# Motor_Control.net
KiCad netlist of a schematic drawn in Altium Designer
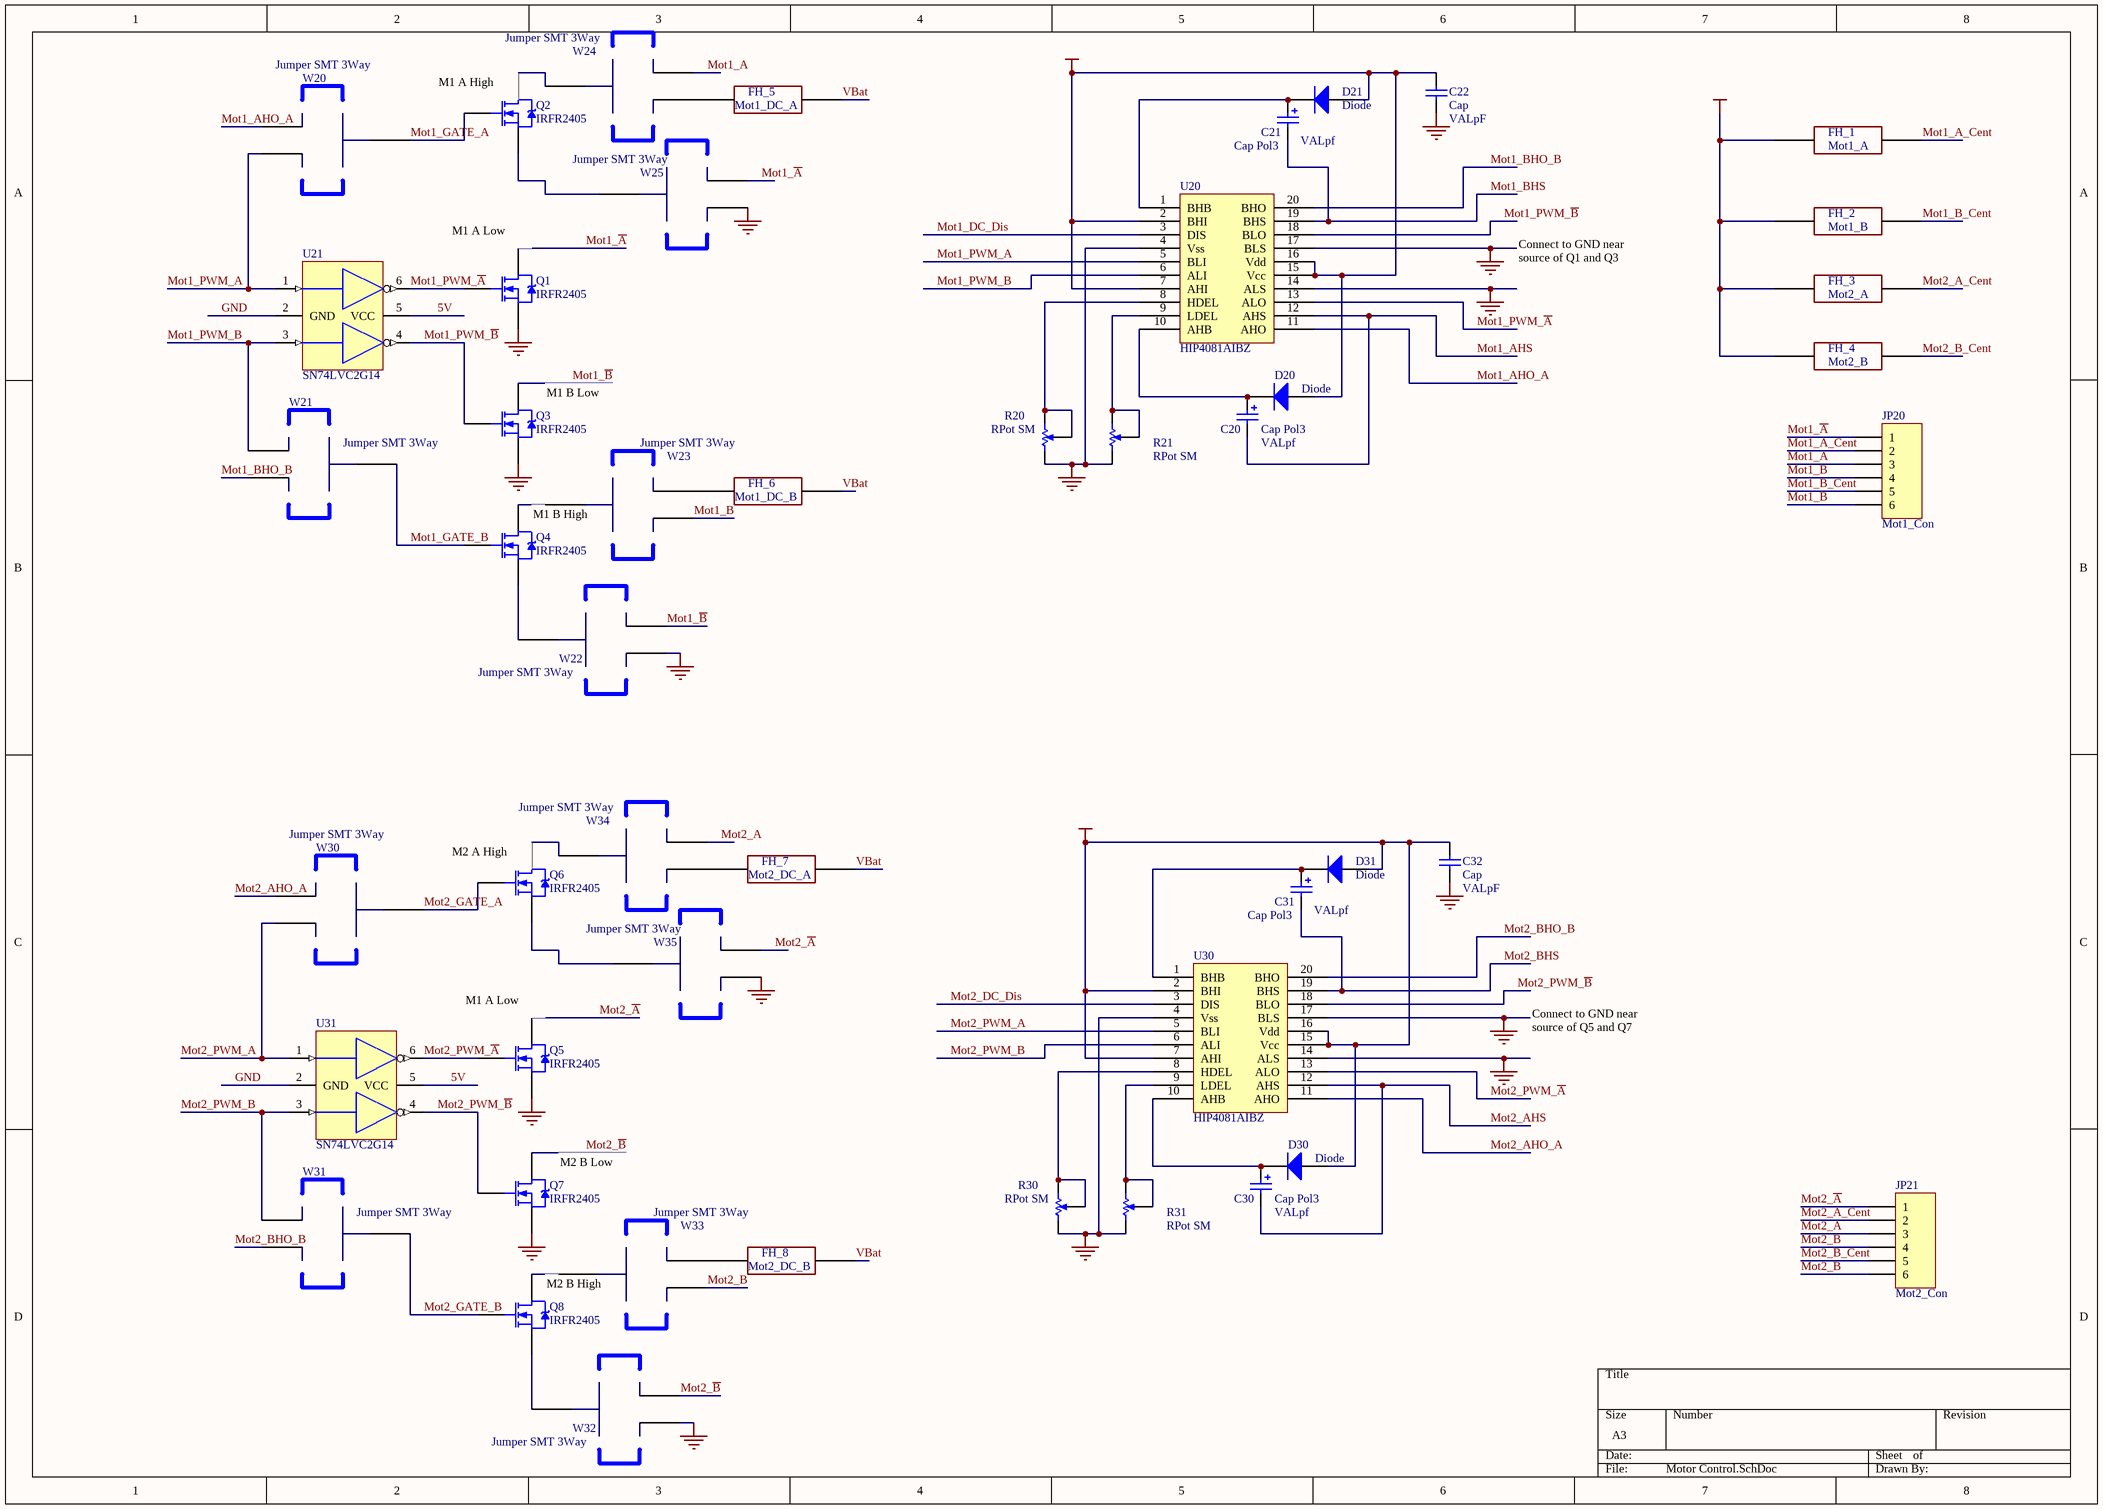
[diagram p0: Motor Control.SchDoc]

(export (version "E")
  (design (tool "Eeschema 10.0.6"))
  (components
    (comp (ref "C20")
      (value "Cap Pol3")
      (footprint "CC2012-0805")
      (description "Polarized Capacitor (Surface Mount)")
      (fields (field (name "ALTIUM_VALUE") "VALpf") (field (name "PUBLISHER") "Altium Limited"))
      (libsource (lib "Miscellaneous Devices") (part "Cap Pol3"))
    )
    (comp (ref "C21")
      (value "Cap Pol3")
      (footprint "CC2012-0805")
      (description "Polarized Capacitor (Surface Mount)")
      (fields (field (name "ALTIUM_VALUE") "VALpf") (field (name "PUBLISHER") "Altium Limited"))
      (libsource (lib "Miscellaneous Devices") (part "Cap Pol3"))
    )
    (comp (ref "C22")
      (value "Cap")
      (footprint "RAD-0.3")
      (description "Capacitor")
      (fields (field (name "ALTIUM_VALUE") "VALpF") (field (name "PUBLISHER") "Altium Limited"))
      (libsource (lib "Miscellaneous Devices") (part "Cap"))
    )
    (comp (ref "C30")
      (value "Cap Pol3")
      (footprint "CC2012-0805")
      (description "Polarized Capacitor (Surface Mount)")
      (fields (field (name "ALTIUM_VALUE") "VALpf") (field (name "PUBLISHER") "Altium Limited"))
      (libsource (lib "Miscellaneous Devices") (part "Cap Pol3"))
    )
    (comp (ref "C31")
      (value "Cap Pol3")
      (footprint "CC2012-0805")
      (description "Polarized Capacitor (Surface Mount)")
      (fields (field (name "ALTIUM_VALUE") "VALpf") (field (name "PUBLISHER") "Altium Limited"))
      (libsource (lib "Miscellaneous Devices") (part "Cap Pol3"))
    )
    (comp (ref "C32")
      (value "Cap")
      (footprint "RAD-0.3")
      (description "Capacitor")
      (fields (field (name "ALTIUM_VALUE") "VALpF") (field (name "PUBLISHER") "Altium Limited"))
      (libsource (lib "Miscellaneous Devices") (part "Cap"))
    )
    (comp (ref "D20")
      (value "Diode")
      (footprint "DSO-C2/X3.3")
      (description "Default Diode")
      (fields (field (name "PUBLISHER") "Altium Limited"))
      (libsource (lib "Miscellaneous Devices") (part "Diode"))
    )
    (comp (ref "D21")
      (value "Diode")
      (footprint "DSO-C2/X3.3")
      (description "Default Diode")
      (fields (field (name "PUBLISHER") "Altium Limited"))
      (libsource (lib "Miscellaneous Devices") (part "Diode"))
    )
    (comp (ref "D30")
      (value "Diode")
      (footprint "DSO-C2/X3.3")
      (description "Default Diode")
      (fields (field (name "PUBLISHER") "Altium Limited"))
      (libsource (lib "Miscellaneous Devices") (part "Diode"))
    )
    (comp (ref "D31")
      (value "Diode")
      (footprint "DSO-C2/X3.3")
      (description "Default Diode")
      (fields (field (name "PUBLISHER") "Altium Limited"))
      (libsource (lib "Miscellaneous Devices") (part "Diode"))
    )
    (comp (ref "FH_1")
      (value "Mot1_A")
      (description "Fuse Holder")
      (libsource (lib "Sumo") (part "Fuse_Holder"))
    )
    (comp (ref "FH_2")
      (value "Mot1_B")
      (description "Fuse Holder")
      (libsource (lib "Sumo") (part "Fuse_Holder"))
    )
    (comp (ref "FH_3")
      (value "Mot2_A")
      (description "Fuse Holder")
      (libsource (lib "Sumo") (part "Fuse_Holder"))
    )
    (comp (ref "FH_4")
      (value "Mot2_B")
      (description "Fuse Holder")
      (libsource (lib "Sumo") (part "Fuse_Holder"))
    )
    (comp (ref "FH_5")
      (value "Mot1_DC_A")
      (description "Fuse Holder")
      (libsource (lib "Sumo") (part "Fuse_Holder"))
    )
    (comp (ref "FH_6")
      (value "Mot1_DC_B")
      (description "Fuse Holder")
      (libsource (lib "Sumo") (part "Fuse_Holder"))
    )
    (comp (ref "FH_7")
      (value "Mot2_DC_A")
      (description "Fuse Holder")
      (libsource (lib "Sumo") (part "Fuse_Holder"))
    )
    (comp (ref "FH_8")
      (value "Mot2_DC_B")
      (description "Fuse Holder")
      (libsource (lib "Sumo") (part "Fuse_Holder"))
    )
    (comp (ref "JP20")
      (value "Mot1_Con")
      (footprint "HDR1X6")
      (description "Header, 6-Pin")
      (fields (field (name "PUBLISHER") "Altium Limited"))
      (libsource (lib "Miscellaneous Connectors") (part "Header 6"))
    )
    (comp (ref "JP21")
      (value "Mot2_Con")
      (footprint "HDR1X6")
      (description "Header, 6-Pin")
      (fields (field (name "PUBLISHER") "Altium Limited"))
      (libsource (lib "Miscellaneous Connectors") (part "Header 6"))
    )
    (comp (ref "Q1")
      (value "IRFR2405")
      (footprint "TO-252AA")
      (description "HEXFET Power MOSFET")
      (fields (field (name "PUBLISHER") "Altium Limited"))
      (libsource (lib "IR Discrete MOSFET - Power") (part "IRFR2405"))
    )
    (comp (ref "Q2")
      (value "IRFR2405")
      (footprint "TO-252AA")
      (description "HEXFET Power MOSFET")
      (fields (field (name "PUBLISHER") "Altium Limited"))
      (libsource (lib "IR Discrete MOSFET - Power") (part "IRFR2405"))
    )
    (comp (ref "Q3")
      (value "IRFR2405")
      (footprint "TO-252AA")
      (description "HEXFET Power MOSFET")
      (fields (field (name "PUBLISHER") "Altium Limited"))
      (libsource (lib "IR Discrete MOSFET - Power") (part "IRFR2405"))
    )
    (comp (ref "Q4")
      (value "IRFR2405")
      (footprint "TO-252AA")
      (description "HEXFET Power MOSFET")
      (fields (field (name "PUBLISHER") "Altium Limited"))
      (libsource (lib "IR Discrete MOSFET - Power") (part "IRFR2405"))
    )
    (comp (ref "Q5")
      (value "IRFR2405")
      (footprint "TO-252AA")
      (description "HEXFET Power MOSFET")
      (fields (field (name "PUBLISHER") "Altium Limited"))
      (libsource (lib "IR Discrete MOSFET - Power") (part "IRFR2405"))
    )
    (comp (ref "Q6")
      (value "IRFR2405")
      (footprint "TO-252AA")
      (description "HEXFET Power MOSFET")
      (fields (field (name "PUBLISHER") "Altium Limited"))
      (libsource (lib "IR Discrete MOSFET - Power") (part "IRFR2405"))
    )
    (comp (ref "Q7")
      (value "IRFR2405")
      (footprint "TO-252AA")
      (description "HEXFET Power MOSFET")
      (fields (field (name "PUBLISHER") "Altium Limited"))
      (libsource (lib "IR Discrete MOSFET - Power") (part "IRFR2405"))
    )
    (comp (ref "Q8")
      (value "IRFR2405")
      (footprint "TO-252AA")
      (description "HEXFET Power MOSFET")
      (fields (field (name "PUBLISHER") "Altium Limited"))
      (libsource (lib "IR Discrete MOSFET - Power") (part "IRFR2405"))
    )
    (comp (ref "R20")
      (value "RPot SM")
      (footprint "POT4MM-2")
      (description "Square Trimming Potentiometer")
      (fields (field (name "PUBLISHER") "Altium Limited"))
      (libsource (lib "Miscellaneous Devices") (part "RPot SM"))
    )
    (comp (ref "R21")
      (value "RPot SM")
      (footprint "POT4MM-2")
      (description "Square Trimming Potentiometer")
      (fields (field (name "PUBLISHER") "Altium Limited"))
      (libsource (lib "Miscellaneous Devices") (part "RPot SM"))
    )
    (comp (ref "R30")
      (value "RPot SM")
      (footprint "POT4MM-2")
      (description "Square Trimming Potentiometer")
      (fields (field (name "PUBLISHER") "Altium Limited"))
      (libsource (lib "Miscellaneous Devices") (part "RPot SM"))
    )
    (comp (ref "R31")
      (value "RPot SM")
      (footprint "POT4MM-2")
      (description "Square Trimming Potentiometer")
      (fields (field (name "PUBLISHER") "Altium Limited"))
      (libsource (lib "Miscellaneous Devices") (part "RPot SM"))
    )
    (comp (ref "U20")
      (value "HIP4081AIBZ")
      (footprint "SOIC20A")
      (description "80V/2.5A Peak, High Frequency Full Bridge FET Driver")
      (libsource (lib "Sumo") (part "HIP4081AIBZ"))
    )
    (comp (ref "U21")
      (value "SN74LVC2G14")
      (footprint "SC70")
      (description "Dual Schmitt-Trigger Inverter")
      (fields (field (name "PUBLISHER") "Altium Limited"))
      (libsource (lib "Sumo") (part "SN74LVC2G14"))
    )
    (comp (ref "U30")
      (value "HIP4081AIBZ")
      (footprint "SOIC20A")
      (description "80V/2.5A Peak, High Frequency Full Bridge FET Driver")
      (libsource (lib "Sumo") (part "HIP4081AIBZ"))
    )
    (comp (ref "U31")
      (value "SN74LVC2G14")
      (footprint "SC70")
      (description "Dual Schmitt-Trigger Inverter")
      (fields (field (name "PUBLISHER") "Altium Limited"))
      (libsource (lib "Sumo") (part "SN74LVC2G14"))
    )
    (comp (ref "W20")
      (value "Jumper SMT 3Way")
      (footprint "Jumper SMT 3 Way")
      (libsource (lib "Schematic Library") (part "Jumper SMT 3Way"))
    )
    (comp (ref "W21")
      (value "Jumper SMT 3Way")
      (footprint "Jumper SMT 3 Way")
      (libsource (lib "Schematic Library") (part "Jumper SMT 3Way"))
    )
    (comp (ref "W22")
      (value "Jumper SMT 3Way")
      (footprint "Jumper SMT 3 Way")
      (libsource (lib "Schematic Library") (part "Jumper SMT 3Way"))
    )
    (comp (ref "W23")
      (value "Jumper SMT 3Way")
      (footprint "Jumper SMT 3 Way")
      (libsource (lib "Schematic Library") (part "Jumper SMT 3Way"))
    )
    (comp (ref "W24")
      (value "Jumper SMT 3Way")
      (footprint "Jumper SMT 3 Way")
      (libsource (lib "Schematic Library") (part "Jumper SMT 3Way"))
    )
    (comp (ref "W25")
      (value "Jumper SMT 3Way")
      (footprint "Jumper SMT 3 Way")
      (libsource (lib "Schematic Library") (part "Jumper SMT 3Way"))
    )
    (comp (ref "W30")
      (value "Jumper SMT 3Way")
      (footprint "Jumper SMT 3 Way")
      (libsource (lib "Schematic Library") (part "Jumper SMT 3Way"))
    )
    (comp (ref "W31")
      (value "Jumper SMT 3Way")
      (footprint "Jumper SMT 3 Way")
      (libsource (lib "Schematic Library") (part "Jumper SMT 3Way"))
    )
    (comp (ref "W32")
      (value "Jumper SMT 3Way")
      (footprint "Jumper SMT 3 Way")
      (libsource (lib "Schematic Library") (part "Jumper SMT 3Way"))
    )
    (comp (ref "W33")
      (value "Jumper SMT 3Way")
      (footprint "Jumper SMT 3 Way")
      (libsource (lib "Schematic Library") (part "Jumper SMT 3Way"))
    )
    (comp (ref "W34")
      (value "Jumper SMT 3Way")
      (footprint "Jumper SMT 3 Way")
      (libsource (lib "Schematic Library") (part "Jumper SMT 3Way"))
    )
    (comp (ref "W35")
      (value "Jumper SMT 3Way")
      (footprint "Jumper SMT 3 Way")
      (libsource (lib "Schematic Library") (part "Jumper SMT 3Way"))
    )
  )
  (nets
    (net (code "1") (name "/5V") (class "Default")
      (node (ref "U21") (pin "5") (pinfunction "VCC_5") (pintype "power_in"))
      (node (ref "U31") (pin "5") (pinfunction "VCC_5") (pintype "power_in"))
    )
    (net (code "2") (name "/Mot1_A") (class "Default")
      (node (ref "JP20") (pin "3") (pinfunction "3_3") (pintype "passive"))
      (node (ref "W24") (pin "2") (pinfunction "Out1_2") (pintype "passive"))
    )
    (net (code "3") (name "/Mot1_AHO_A") (class "Default")
      (node (ref "U20") (pin "11") (pinfunction "AHO_11") (pintype "passive"))
      (node (ref "W20") (pin "3") (pinfunction "Out2_3") (pintype "passive"))
    )
    (net (code "4") (name "/Mot1_AHS") (class "Default")
      (node (ref "C20") (pin "2") (pinfunction "2_2") (pintype "passive"))
      (node (ref "U20") (pin "12") (pinfunction "AHS_12") (pintype "passive"))
    )
    (net (code "5") (name "/Mot1_A_Cent") (class "Default")
      (node (ref "FH_1") (pin "2") (pinfunction "2_2") (pintype "passive"))
      (node (ref "JP20") (pin "2") (pinfunction "2_2") (pintype "passive"))
    )
    (net (code "6") (name "/Mot1_B") (class "Default")
      (node (ref "JP20") (pin "6") (pinfunction "6_6") (pintype "passive"))
      (node (ref "W23") (pin "3") (pinfunction "Out2_3") (pintype "passive"))
    )
    (net (code "7") (name "/Mot1_BHO_B") (class "Default")
      (node (ref "U20") (pin "20") (pinfunction "BHO_20") (pintype "passive"))
      (node (ref "W21") (pin "2") (pinfunction "Out1_2") (pintype "passive"))
    )
    (net (code "8") (name "/Mot1_BHS") (class "Default")
      (node (ref "C21") (pin "2") (pinfunction "2_2") (pintype "passive"))
      (node (ref "U20") (pin "19") (pinfunction "BHS_19") (pintype "passive"))
    )
    (net (code "9") (name "/Mot1_B_Cent") (class "Default")
      (node (ref "FH_2") (pin "2") (pinfunction "2_2") (pintype "passive"))
      (node (ref "JP20") (pin "5") (pinfunction "5_5") (pintype "passive"))
    )
    (net (code "10") (name "/Mot1_DC_Dis") (class "Default")
      (node (ref "U20") (pin "3") (pinfunction "DIS_3") (pintype "passive"))
    )
    (net (code "11") (name "/Mot1_GATE_A") (class "Default")
      (node (ref "Q2") (pin "1") (pinfunction "G_1") (pintype "passive"))
      (node (ref "W20") (pin "1") (pinfunction "In_1") (pintype "passive"))
    )
    (net (code "12") (name "/Mot1_GATE_B") (class "Default")
      (node (ref "Q4") (pin "1") (pinfunction "G_1") (pintype "passive"))
      (node (ref "W21") (pin "1") (pinfunction "In_1") (pintype "passive"))
    )
    (net (code "13") (name "/Mot1_PWM_A") (class "Default")
      (node (ref "U20") (pin "5") (pinfunction "BLI_5") (pintype "passive"))
      (node (ref "U21") (pin "1") (pinfunction "A_1") (pintype "input"))
      (node (ref "W20") (pin "2") (pinfunction "Out1_2") (pintype "passive"))
    )
    (net (code "14") (name "/Mot1_PWM_B") (class "Default")
      (node (ref "U20") (pin "6") (pinfunction "ALI_6") (pintype "passive"))
      (node (ref "U21") (pin "3") (pinfunction "A_3") (pintype "input"))
      (node (ref "W21") (pin "3") (pinfunction "Out2_3") (pintype "passive"))
    )
    (net (code "15") (name "/Mot1_PWM_~{A}") (class "Default")
      (node (ref "Q1") (pin "1") (pinfunction "G_1") (pintype "passive"))
      (node (ref "U20") (pin "13") (pinfunction "ALO_13") (pintype "passive"))
      (node (ref "U21") (pin "6") (pinfunction "Y_6") (pintype "output"))
    )
    (net (code "16") (name "/Mot1_PWM_~{B}") (class "Default")
      (node (ref "Q3") (pin "1") (pinfunction "G_1") (pintype "passive"))
      (node (ref "U20") (pin "18") (pinfunction "BLO_18") (pintype "passive"))
      (node (ref "U21") (pin "4") (pinfunction "Y_4") (pintype "output"))
    )
    (net (code "17") (name "/Mot1_~{A}") (class "Default")
      (node (ref "JP20") (pin "1") (pinfunction "1_1") (pintype "passive"))
      (node (ref "Q1") (pin "4") (pinfunction "D_4") (pintype "passive"))
      (node (ref "W25") (pin "2") (pinfunction "Out1_2") (pintype "passive"))
    )
    (net (code "18") (name "/Mot1_~{B}") (class "Default")
      (node (ref "JP20") (pin "4") (pinfunction "4_4") (pintype "passive"))
      (node (ref "Q3") (pin "4") (pinfunction "D_4") (pintype "passive"))
      (node (ref "W22") (pin "2") (pinfunction "Out1_2") (pintype "passive"))
    )
    (net (code "19") (name "/Mot2_A") (class "Default")
      (node (ref "JP21") (pin "3") (pinfunction "3_3") (pintype "passive"))
      (node (ref "W34") (pin "2") (pinfunction "Out1_2") (pintype "passive"))
    )
    (net (code "20") (name "/Mot2_AHO_A") (class "Default")
      (node (ref "U30") (pin "11") (pinfunction "AHO_11") (pintype "passive"))
      (node (ref "W30") (pin "3") (pinfunction "Out2_3") (pintype "passive"))
    )
    (net (code "21") (name "/Mot2_AHS") (class "Default")
      (node (ref "C30") (pin "2") (pinfunction "2_2") (pintype "passive"))
      (node (ref "U30") (pin "12") (pinfunction "AHS_12") (pintype "passive"))
    )
    (net (code "22") (name "/Mot2_A_Cent") (class "Default")
      (node (ref "FH_3") (pin "2") (pinfunction "2_2") (pintype "passive"))
      (node (ref "JP21") (pin "2") (pinfunction "2_2") (pintype "passive"))
    )
    (net (code "23") (name "/Mot2_B") (class "Default")
      (node (ref "JP21") (pin "6") (pinfunction "6_6") (pintype "passive"))
      (node (ref "W33") (pin "3") (pinfunction "Out2_3") (pintype "passive"))
    )
    (net (code "24") (name "/Mot2_BHO_B") (class "Default")
      (node (ref "U30") (pin "20") (pinfunction "BHO_20") (pintype "passive"))
      (node (ref "W31") (pin "2") (pinfunction "Out1_2") (pintype "passive"))
    )
    (net (code "25") (name "/Mot2_BHS") (class "Default")
      (node (ref "C31") (pin "2") (pinfunction "2_2") (pintype "passive"))
      (node (ref "U30") (pin "19") (pinfunction "BHS_19") (pintype "passive"))
    )
    (net (code "26") (name "/Mot2_B_Cent") (class "Default")
      (node (ref "FH_4") (pin "2") (pinfunction "2_2") (pintype "passive"))
      (node (ref "JP21") (pin "5") (pinfunction "5_5") (pintype "passive"))
    )
    (net (code "27") (name "/Mot2_DC_Dis") (class "Default")
      (node (ref "U30") (pin "3") (pinfunction "DIS_3") (pintype "passive"))
    )
    (net (code "28") (name "/Mot2_GATE_A") (class "Default")
      (node (ref "Q6") (pin "1") (pinfunction "G_1") (pintype "passive"))
      (node (ref "W30") (pin "1") (pinfunction "In_1") (pintype "passive"))
    )
    (net (code "29") (name "/Mot2_GATE_B") (class "Default")
      (node (ref "Q8") (pin "1") (pinfunction "G_1") (pintype "passive"))
      (node (ref "W31") (pin "1") (pinfunction "In_1") (pintype "passive"))
    )
    (net (code "30") (name "/Mot2_PWM_A") (class "Default")
      (node (ref "U30") (pin "5") (pinfunction "BLI_5") (pintype "passive"))
      (node (ref "U31") (pin "1") (pinfunction "A_1") (pintype "input"))
      (node (ref "W30") (pin "2") (pinfunction "Out1_2") (pintype "passive"))
    )
    (net (code "31") (name "/Mot2_PWM_B") (class "Default")
      (node (ref "U30") (pin "6") (pinfunction "ALI_6") (pintype "passive"))
      (node (ref "U31") (pin "3") (pinfunction "A_3") (pintype "input"))
      (node (ref "W31") (pin "3") (pinfunction "Out2_3") (pintype "passive"))
    )
    (net (code "32") (name "/Mot2_PWM_~{A}") (class "Default")
      (node (ref "Q5") (pin "1") (pinfunction "G_1") (pintype "passive"))
      (node (ref "U30") (pin "13") (pinfunction "ALO_13") (pintype "passive"))
      (node (ref "U31") (pin "6") (pinfunction "Y_6") (pintype "output"))
    )
    (net (code "33") (name "/Mot2_PWM_~{B}") (class "Default")
      (node (ref "Q7") (pin "1") (pinfunction "G_1") (pintype "passive"))
      (node (ref "U30") (pin "18") (pinfunction "BLO_18") (pintype "passive"))
      (node (ref "U31") (pin "4") (pinfunction "Y_4") (pintype "output"))
    )
    (net (code "34") (name "/Mot2_~{A}") (class "Default")
      (node (ref "JP21") (pin "1") (pinfunction "1_1") (pintype "passive"))
      (node (ref "Q5") (pin "4") (pinfunction "D_4") (pintype "passive"))
      (node (ref "W35") (pin "2") (pinfunction "Out1_2") (pintype "passive"))
    )
    (net (code "35") (name "/Mot2_~{B}") (class "Default")
      (node (ref "JP21") (pin "4") (pinfunction "4_4") (pintype "passive"))
      (node (ref "Q7") (pin "4") (pinfunction "D_4") (pintype "passive"))
      (node (ref "W32") (pin "2") (pinfunction "Out1_2") (pintype "passive"))
    )
    (net (code "36") (name "12V") (class "Default")
      (node (ref "C22") (pin "2") (pinfunction "2_2") (pintype "passive"))
      (node (ref "C32") (pin "2") (pinfunction "2_2") (pintype "passive"))
      (node (ref "D20") (pin "1") (pinfunction "A_1") (pintype "passive"))
      (node (ref "D21") (pin "1") (pinfunction "A_1") (pintype "passive"))
      (node (ref "D30") (pin "1") (pinfunction "A_1") (pintype "passive"))
      (node (ref "D31") (pin "1") (pinfunction "A_1") (pintype "passive"))
      (node (ref "U20") (pin "15") (pinfunction "Vcc_15") (pintype "passive"))
      (node (ref "U20") (pin "16") (pinfunction "Vdd_16") (pintype "passive"))
      (node (ref "U20") (pin "2") (pinfunction "BHI_2") (pintype "passive"))
      (node (ref "U20") (pin "7") (pinfunction "AHI_7") (pintype "passive"))
      (node (ref "U30") (pin "15") (pinfunction "Vcc_15") (pintype "passive"))
      (node (ref "U30") (pin "16") (pinfunction "Vdd_16") (pintype "passive"))
      (node (ref "U30") (pin "2") (pinfunction "BHI_2") (pintype "passive"))
      (node (ref "U30") (pin "7") (pinfunction "AHI_7") (pintype "passive"))
    )
    (net (code "37") (name "GND") (class "Default")
      (node (ref "C22") (pin "1") (pinfunction "1_1") (pintype "passive"))
      (node (ref "C32") (pin "1") (pinfunction "1_1") (pintype "passive"))
      (node (ref "Q1") (pin "3") (pinfunction "S_3") (pintype "passive"))
      (node (ref "Q3") (pin "3") (pinfunction "S_3") (pintype "passive"))
      (node (ref "Q5") (pin "3") (pinfunction "S_3") (pintype "passive"))
      (node (ref "Q7") (pin "3") (pinfunction "S_3") (pintype "passive"))
      (node (ref "R20") (pin "CCW") (pinfunction "-_CCW") (pintype "passive"))
      (node (ref "R21") (pin "CCW") (pinfunction "-_CCW") (pintype "passive"))
      (node (ref "R30") (pin "CCW") (pinfunction "-_CCW") (pintype "passive"))
      (node (ref "R31") (pin "CCW") (pinfunction "-_CCW") (pintype "passive"))
      (node (ref "U20") (pin "14") (pinfunction "ALS_14") (pintype "passive"))
      (node (ref "U20") (pin "17") (pinfunction "BLS_17") (pintype "passive"))
      (node (ref "U20") (pin "4") (pinfunction "Vss_4") (pintype "passive"))
      (node (ref "U21") (pin "2") (pinfunction "GND_2") (pintype "power_in"))
      (node (ref "U30") (pin "14") (pinfunction "ALS_14") (pintype "passive"))
      (node (ref "U30") (pin "17") (pinfunction "BLS_17") (pintype "passive"))
      (node (ref "U30") (pin "4") (pinfunction "Vss_4") (pintype "passive"))
      (node (ref "U31") (pin "2") (pinfunction "GND_2") (pintype "power_in"))
      (node (ref "W22") (pin "3") (pinfunction "Out2_3") (pintype "passive"))
      (node (ref "W25") (pin "3") (pinfunction "Out2_3") (pintype "passive"))
      (node (ref "W32") (pin "3") (pinfunction "Out2_3") (pintype "passive"))
      (node (ref "W35") (pin "3") (pinfunction "Out2_3") (pintype "passive"))
    )
    (net (code "38") (name "Net-(D20-K)") (class "Default")
      (node (ref "C20") (pin "1") (pinfunction "1_1") (pintype "passive"))
      (node (ref "D20") (pin "2") (pinfunction "K_2") (pintype "passive"))
      (node (ref "U20") (pin "10") (pinfunction "AHB_10") (pintype "passive"))
    )
    (net (code "39") (name "Net-(D21-K)") (class "Default")
      (node (ref "C21") (pin "1") (pinfunction "1_1") (pintype "passive"))
      (node (ref "D21") (pin "2") (pinfunction "K_2") (pintype "passive"))
      (node (ref "U20") (pin "1") (pinfunction "BHB_1") (pintype "passive"))
    )
    (net (code "40") (name "Net-(D30-K)") (class "Default")
      (node (ref "C30") (pin "1") (pinfunction "1_1") (pintype "passive"))
      (node (ref "D30") (pin "2") (pinfunction "K_2") (pintype "passive"))
      (node (ref "U30") (pin "10") (pinfunction "AHB_10") (pintype "passive"))
    )
    (net (code "41") (name "Net-(D31-K)") (class "Default")
      (node (ref "C31") (pin "1") (pinfunction "1_1") (pintype "passive"))
      (node (ref "D31") (pin "2") (pinfunction "K_2") (pintype "passive"))
      (node (ref "U30") (pin "1") (pinfunction "BHB_1") (pintype "passive"))
    )
    (net (code "42") (name "Net-(Q2-D)") (class "Default")
      (node (ref "Q2") (pin "4") (pinfunction "D_4") (pintype "passive"))
      (node (ref "W24") (pin "1") (pinfunction "In_1") (pintype "passive"))
    )
    (net (code "43") (name "Net-(Q2-S)") (class "Default")
      (node (ref "Q2") (pin "3") (pinfunction "S_3") (pintype "passive"))
      (node (ref "W25") (pin "1") (pinfunction "In_1") (pintype "passive"))
    )
    (net (code "44") (name "Net-(Q4-D)") (class "Default")
      (node (ref "Q4") (pin "4") (pinfunction "D_4") (pintype "passive"))
      (node (ref "W23") (pin "1") (pinfunction "In_1") (pintype "passive"))
    )
    (net (code "45") (name "Net-(Q4-S)") (class "Default")
      (node (ref "Q4") (pin "3") (pinfunction "S_3") (pintype "passive"))
      (node (ref "W22") (pin "1") (pinfunction "In_1") (pintype "passive"))
    )
    (net (code "46") (name "Net-(Q6-D)") (class "Default")
      (node (ref "Q6") (pin "4") (pinfunction "D_4") (pintype "passive"))
      (node (ref "W34") (pin "1") (pinfunction "In_1") (pintype "passive"))
    )
    (net (code "47") (name "Net-(Q6-S)") (class "Default")
      (node (ref "Q6") (pin "3") (pinfunction "S_3") (pintype "passive"))
      (node (ref "W35") (pin "1") (pinfunction "In_1") (pintype "passive"))
    )
    (net (code "48") (name "Net-(Q8-D)") (class "Default")
      (node (ref "Q8") (pin "4") (pinfunction "D_4") (pintype "passive"))
      (node (ref "W33") (pin "1") (pinfunction "In_1") (pintype "passive"))
    )
    (net (code "49") (name "Net-(Q8-S)") (class "Default")
      (node (ref "Q8") (pin "3") (pinfunction "S_3") (pintype "passive"))
      (node (ref "W32") (pin "1") (pinfunction "In_1") (pintype "passive"))
    )
    (net (code "50") (name "Net-(R20-+)") (class "Default")
      (node (ref "R20") (pin "CW") (pinfunction "+_CW") (pintype "passive"))
      (node (ref "R20") (pin "W") (pintype "passive"))
      (node (ref "U20") (pin "8") (pinfunction "HDEL_8") (pintype "passive"))
    )
    (net (code "51") (name "Net-(R21-+)") (class "Default")
      (node (ref "R21") (pin "CW") (pinfunction "+_CW") (pintype "passive"))
      (node (ref "R21") (pin "W") (pintype "passive"))
      (node (ref "U20") (pin "9") (pinfunction "LDEL_9") (pintype "passive"))
    )
    (net (code "52") (name "Net-(R30-+)") (class "Default")
      (node (ref "R30") (pin "CW") (pinfunction "+_CW") (pintype "passive"))
      (node (ref "R30") (pin "W") (pintype "passive"))
      (node (ref "U30") (pin "8") (pinfunction "HDEL_8") (pintype "passive"))
    )
    (net (code "53") (name "Net-(R31-+)") (class "Default")
      (node (ref "R31") (pin "CW") (pinfunction "+_CW") (pintype "passive"))
      (node (ref "R31") (pin "W") (pintype "passive"))
      (node (ref "U30") (pin "9") (pinfunction "LDEL_9") (pintype "passive"))
    )
    (net (code "54") (name "Net-(W23-Out1)") (class "Default")
      (node (ref "FH_6") (pin "1") (pinfunction "1_1") (pintype "passive"))
      (node (ref "W23") (pin "2") (pinfunction "Out1_2") (pintype "passive"))
    )
    (net (code "55") (name "Net-(W24-Out2)") (class "Default")
      (node (ref "FH_5") (pin "1") (pinfunction "1_1") (pintype "passive"))
      (node (ref "W24") (pin "3") (pinfunction "Out2_3") (pintype "passive"))
    )
    (net (code "56") (name "Net-(W33-Out1)") (class "Default")
      (node (ref "FH_8") (pin "1") (pinfunction "1_1") (pintype "passive"))
      (node (ref "W33") (pin "2") (pinfunction "Out1_2") (pintype "passive"))
    )
    (net (code "57") (name "Net-(W34-Out2)") (class "Default")
      (node (ref "FH_7") (pin "1") (pinfunction "1_1") (pintype "passive"))
      (node (ref "W34") (pin "3") (pinfunction "Out2_3") (pintype "passive"))
    )
    (net (code "58") (name "VBat") (class "Default")
      (node (ref "FH_1") (pin "1") (pinfunction "1_1") (pintype "passive"))
      (node (ref "FH_2") (pin "1") (pinfunction "1_1") (pintype "passive"))
      (node (ref "FH_3") (pin "1") (pinfunction "1_1") (pintype "passive"))
      (node (ref "FH_4") (pin "1") (pinfunction "1_1") (pintype "passive"))
      (node (ref "FH_5") (pin "2") (pinfunction "2_2") (pintype "passive"))
      (node (ref "FH_6") (pin "2") (pinfunction "2_2") (pintype "passive"))
      (node (ref "FH_7") (pin "2") (pinfunction "2_2") (pintype "passive"))
      (node (ref "FH_8") (pin "2") (pinfunction "2_2") (pintype "passive"))
    )
  )
)
